# User_interface.net
KiCad netlist of a schematic drawn in Altium Designer
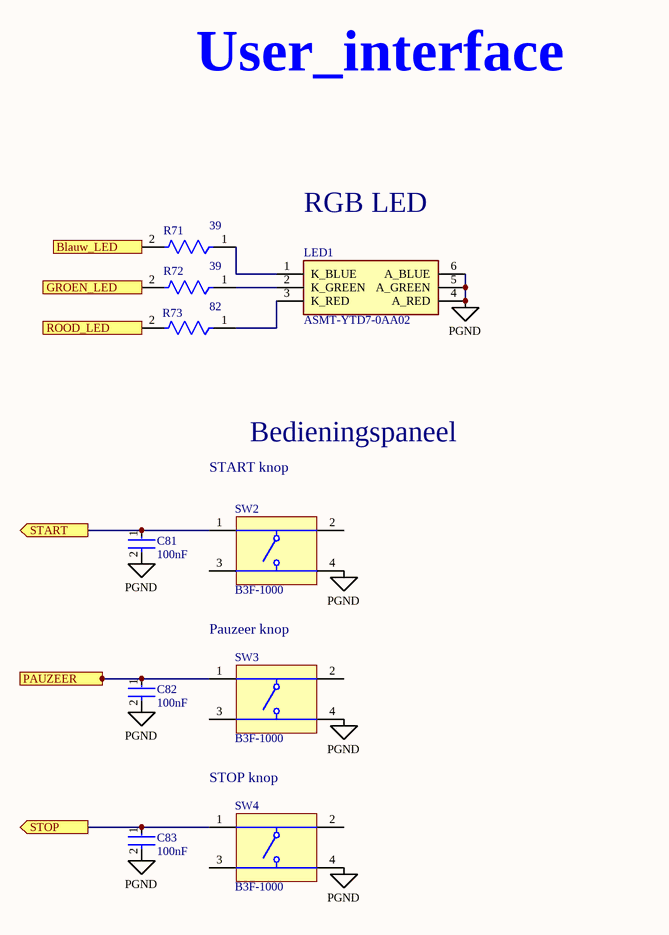
[diagram p0: User_interface.SchDoc]

(export (version "E")
  (design (tool "Eeschema 10.0.6"))
  (components
    (comp (ref "C81")
      (value "100nF")
      (footprint "FP-GRM15-MFG")
      (description "CAP CER 0.1UF 16V X7R 0402")
      (fields (field (name "MANUFACTURER PART NUMBER") "GRM155R71C104KA88D") (field (name "TOLERANCE") "10%"))
      (libsource (lib "Altium Content Vault") (part "236180d848d6139a670b325ea6854c9"))
    )
    (comp (ref "C82")
      (value "100nF")
      (footprint "FP-GRM15-MFG")
      (description "CAP CER 0.1UF 16V X7R 0402")
      (fields (field (name "MANUFACTURER PART NUMBER") "GRM155R71C104KA88D") (field (name "TOLERANCE") "10%"))
      (libsource (lib "Altium Content Vault") (part "236180d848d6139a670b325ea6854c9"))
    )
    (comp (ref "C83")
      (value "100nF")
      (footprint "FP-GRM15-MFG")
      (description "CAP CER 0.1UF 16V X7R 0402")
      (fields (field (name "MANUFACTURER PART NUMBER") "GRM155R71C104KA88D") (field (name "TOLERANCE") "10%"))
      (libsource (lib "Altium Content Vault") (part "236180d848d6139a670b325ea6854c9"))
    )
    (comp (ref "LED1")
      (value "ASMT-YTD7-0AA02")
      (footprint "SamacSys:ASMTYTD70AA02")
      (description "LED")
      (fields (field (name "MOUSER PART NUMBER") "630-ASMT-YTD7-0AA02"))
      (libsource (lib "*") (part "ASMT-YTD7-0AA02"))
    )
    (comp (ref "R71")
      (value "39")
      (footprint "FP-RC1608-IPC_B")
      (fields (field (name "TOLERANCE") "1%"))
      (libsource (lib "Altium Content Vault") (part "1029c3af85768c4190bb7ad29bc67b5"))
    )
    (comp (ref "R72")
      (value "39")
      (footprint "FP-RC1608-IPC_B")
      (fields (field (name "TOLERANCE") "1%"))
      (libsource (lib "Altium Content Vault") (part "1029c3af85768c4190bb7ad29bc67b5"))
    )
    (comp (ref "R73")
      (value "82")
      (footprint "FP-RC1608-IPC_B")
      (fields (field (name "TOLERANCE") "1%"))
      (libsource (lib "Altium Content Vault") (part "1029c3af85768c4190bb7ad29bc67b5"))
    )
    (comp (ref "SW2")
      (value "B3F-1000")
      (footprint "OMRON-B3F-1000-4_V")
      (description "Tactile Switch, SPST-NO, 0.05 A, 5 to 24 V, -25 to 70 degC, 4-Pin THD, RoHS, Bulk")
      (libsource (lib "Altium Content Vault") (part "SW-SPST-4_A"))
    )
    (comp (ref "SW3")
      (value "B3F-1000")
      (footprint "OMRON-B3F-1000-4_V")
      (description "Tactile Switch, SPST-NO, 0.05 A, 5 to 24 V, -25 to 70 degC, 4-Pin THD, RoHS, Bulk")
      (libsource (lib "Altium Content Vault") (part "SW-SPST-4_A"))
    )
    (comp (ref "SW4")
      (value "B3F-1000")
      (footprint "OMRON-B3F-1000-4_V")
      (description "Tactile Switch, SPST-NO, 0.05 A, 5 to 24 V, -25 to 70 degC, 4-Pin THD, RoHS, Bulk")
      (libsource (lib "Altium Content Vault") (part "SW-SPST-4_A"))
    )
  )
  (nets
    (net (code "1") (name "/Blauw_LED") (class "Default")
      (node (ref "R71") (pin "2") (pinfunction "2_2") (pintype "passive"))
    )
    (net (code "2") (name "/GROEN_LED") (class "Default")
      (node (ref "R72") (pin "2") (pinfunction "2_2") (pintype "passive"))
    )
    (net (code "3") (name "/PAUZEER") (class "Default")
      (node (ref "C82") (pin "1") (pinfunction "1_1") (pintype "passive"))
      (node (ref "SW3") (pin "1") (pinfunction "1_1") (pintype "passive"))
    )
    (net (code "4") (name "/ROOD_LED") (class "Default")
      (node (ref "R73") (pin "2") (pinfunction "2_2") (pintype "passive"))
    )
    (net (code "5") (name "/START") (class "Default")
      (node (ref "C81") (pin "1") (pinfunction "1_1") (pintype "passive"))
      (node (ref "SW2") (pin "1") (pinfunction "1_1") (pintype "passive"))
    )
    (net (code "6") (name "/STOP") (class "Default")
      (node (ref "C83") (pin "1") (pinfunction "1_1") (pintype "passive"))
      (node (ref "SW4") (pin "1") (pinfunction "1_1") (pintype "passive"))
    )
    (net (code "7") (name "Net-(LED1-K_BLUE)") (class "Default")
      (node (ref "LED1") (pin "1") (pinfunction "K_BLUE_1") (pintype "passive"))
      (node (ref "R71") (pin "1") (pinfunction "1_1") (pintype "passive"))
    )
    (net (code "8") (name "Net-(LED1-K_GREEN)") (class "Default")
      (node (ref "LED1") (pin "2") (pinfunction "K_GREEN_2") (pintype "passive"))
      (node (ref "R72") (pin "1") (pinfunction "1_1") (pintype "passive"))
    )
    (net (code "9") (name "Net-(LED1-K_RED)") (class "Default")
      (node (ref "LED1") (pin "3") (pinfunction "K_RED_3") (pintype "passive"))
      (node (ref "R73") (pin "1") (pinfunction "1_1") (pintype "passive"))
    )
    (net (code "10") (name "PGND") (class "Default")
      (node (ref "C81") (pin "2") (pinfunction "2_2") (pintype "passive"))
      (node (ref "C82") (pin "2") (pinfunction "2_2") (pintype "passive"))
      (node (ref "C83") (pin "2") (pinfunction "2_2") (pintype "passive"))
      (node (ref "LED1") (pin "4") (pinfunction "A_RED_4") (pintype "passive"))
      (node (ref "LED1") (pin "5") (pinfunction "A_GREEN_5") (pintype "passive"))
      (node (ref "LED1") (pin "6") (pinfunction "A_BLUE_6") (pintype "passive"))
      (node (ref "SW2") (pin "4") (pinfunction "4_4") (pintype "passive"))
      (node (ref "SW3") (pin "4") (pinfunction "4_4") (pintype "passive"))
      (node (ref "SW4") (pin "4") (pinfunction "4_4") (pintype "passive"))
    )
    (net (code "11") (name "unconnected-(SW2-Pad2)") (class "Default")
      (node (ref "SW2") (pin "2") (pinfunction "2_2") (pintype "passive"))
    )
    (net (code "12") (name "unconnected-(SW2-Pad3)") (class "Default")
      (node (ref "SW2") (pin "3") (pinfunction "3_3") (pintype "passive"))
    )
    (net (code "13") (name "unconnected-(SW3-Pad2)") (class "Default")
      (node (ref "SW3") (pin "2") (pinfunction "2_2") (pintype "passive"))
    )
    (net (code "14") (name "unconnected-(SW3-Pad3)") (class "Default")
      (node (ref "SW3") (pin "3") (pinfunction "3_3") (pintype "passive"))
    )
    (net (code "15") (name "unconnected-(SW4-Pad2)") (class "Default")
      (node (ref "SW4") (pin "2") (pinfunction "2_2") (pintype "passive"))
    )
    (net (code "16") (name "unconnected-(SW4-Pad3)") (class "Default")
      (node (ref "SW4") (pin "3") (pinfunction "3_3") (pintype "passive"))
    )
  )
)
